# Aux_Lights_Power_Conversion.net
KiCad netlist of a schematic drawn in Altium Designer
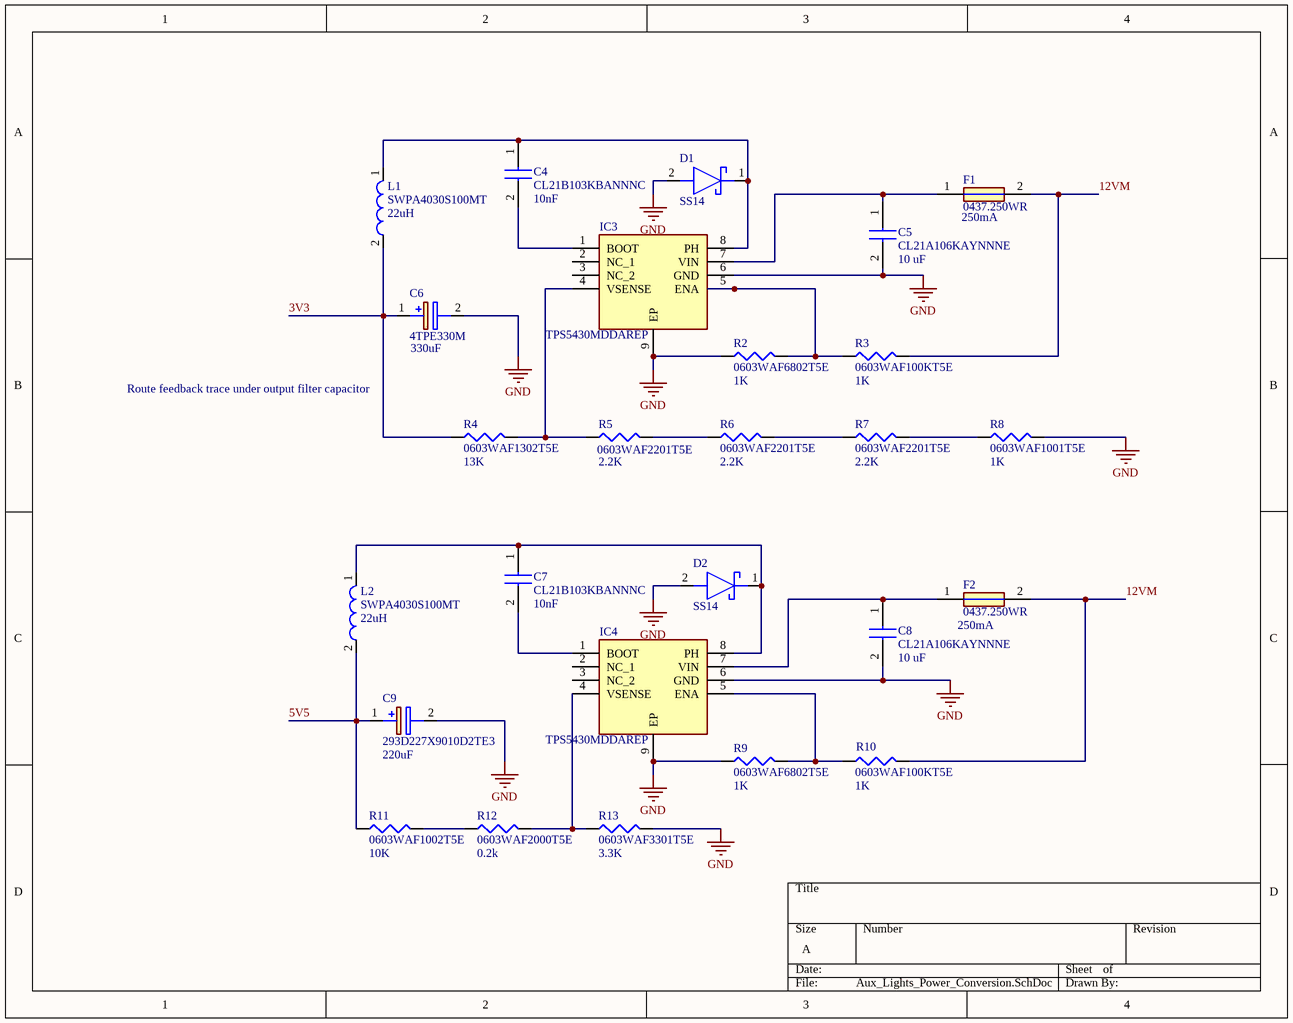
[diagram p0: Aux_Lights_Power_Conversion.SchDoc]

(export (version "E")
  (design (tool "Eeschema 10.0.6"))
  (components
    (comp (ref "C4")
      (value "CL21B103KBANNNC")
      (footprint "SteeringWheelParts:CAPC2012X65N")
      (description "Capacitor")
      (fields (field (name "ALTIUM_VALUE") "10nF"))
      (libsource (lib "SteeringWheelParts") (part "CL21B103KBANNNC"))
    )
    (comp (ref "C5")
      (value "CL21A106KAYNNNE")
      (footprint "SteeringWheelParts:CAPC2012X145N")
      (description "Capacitor")
      (fields (field (name "ALTIUM_VALUE") "10 uF"))
      (libsource (lib "*") (part "CL21A106KAYNNNE"))
    )
    (comp (ref "C6")
      (value "4TPE330M")
      (footprint "SG_Common:POSCAP_D12_D15_D15E_D2E_D2_D3L_D4")
      (description "Capacitor Polarised")
      (fields (field (name "ALTIUM_VALUE") "330uF"))
      (libsource (lib "*") (part "4TPE330M"))
    )
    (comp (ref "C7")
      (value "CL21B103KBANNNC")
      (footprint "SteeringWheelParts:CAPC2012X65N")
      (description "Capacitor")
      (fields (field (name "ALTIUM_VALUE") "10nF"))
      (libsource (lib "SteeringWheelParts") (part "CL21B103KBANNNC"))
    )
    (comp (ref "C8")
      (value "CL21A106KAYNNNE")
      (footprint "SteeringWheelParts:CAPC2012X145N")
      (description "Capacitor")
      (fields (field (name "ALTIUM_VALUE") "10 uF"))
      (libsource (lib "*") (part "CL21A106KAYNNNE"))
    )
    (comp (ref "C9")
      (value "293D227X9010D2TE3")
      (footprint "SteeringWheelParts:CAPPM7343X310N")
      (description "Capacitor Polarised")
      (fields (field (name "ALTIUM_VALUE") "220uF"))
      (libsource (lib "*") (part "293D227X9010D2TE3"))
    )
    (comp (ref "D1")
      (value "SS14")
      (footprint "SteeringWheelParts:DIONM5327X242N")
      (description "Schottky Diode")
      (libsource (lib "SteeringWheelParts") (part "SS14"))
    )
    (comp (ref "D2")
      (value "SS14")
      (footprint "SteeringWheelParts:DIONM5327X242N")
      (description "Schottky Diode")
      (libsource (lib "SteeringWheelParts") (part "SS14"))
    )
    (comp (ref "F1")
      (value "0437.250WR")
      (footprint "SteeringWheelParts:FUSC3216X86N")
      (description "Fuse")
      (fields (field (name "ALTIUM_VALUE") "250mA"))
      (libsource (lib "*") (part "0437.250WR"))
    )
    (comp (ref "F2")
      (value "0437.250WR")
      (footprint "SteeringWheelParts:FUSC3216X86N")
      (description "Fuse")
      (fields (field (name "ALTIUM_VALUE") "250mA"))
      (libsource (lib "*") (part "0437.250WR"))
    )
    (comp (ref "IC3")
      (value "TPS5430MDDAREP")
      (footprint "SteeringWheelParts:SOIC127P600X170-9N")
      (description "Integrated Circuit")
      (fields (field (name "MOUSER2 PART NUMBER") "595-TPS5430MDDAREP"))
      (libsource (lib "SteeringWheelParts") (part "TPS5430MDDAREP"))
    )
    (comp (ref "IC4")
      (value "TPS5430MDDAREP")
      (footprint "SteeringWheelParts:SOIC127P600X170-9N")
      (description "Integrated Circuit")
      (fields (field (name "MOUSER2 PART NUMBER") "595-TPS5430MDDAREP"))
      (libsource (lib "SteeringWheelParts") (part "TPS5430MDDAREP"))
    )
    (comp (ref "L1")
      (value "SWPA4030S100MT")
      (footprint "SWPA4030S100MT")
      (fields (field (name "ALTIUM_VALUE") "22uH"))
      (libsource (lib "SG_Common") (part "SWPA4030S100MT"))
    )
    (comp (ref "L2")
      (value "SWPA4030S100MT")
      (footprint "SWPA4030S100MT")
      (fields (field (name "ALTIUM_VALUE") "22uH"))
      (libsource (lib "SG_Common") (part "SWPA4030S100MT"))
    )
    (comp (ref "R2")
      (value "0603WAF6802T5E")
      (footprint "J1-0603")
      (description "Resistor")
      (fields (field (name "ALTIUM_VALUE") "1K") (field (name "PUBLISHER") "Altium Limited"))
      (libsource (lib "Miscellaneous Devices") (part "Res3"))
    )
    (comp (ref "R3")
      (value "0603WAF100KT5E")
      (footprint "J1-0603")
      (description "Resistor")
      (fields (field (name "ALTIUM_VALUE") "1K") (field (name "PUBLISHER") "Altium Limited"))
      (libsource (lib "Miscellaneous Devices") (part "Res3"))
    )
    (comp (ref "R4")
      (value "0603WAF1302T5E")
      (footprint "J1-0603")
      (description "Resistor")
      (fields (field (name "ALTIUM_VALUE") "13K") (field (name "PUBLISHER") "Altium Limited"))
      (libsource (lib "Miscellaneous Devices") (part "Res3"))
    )
    (comp (ref "R5")
      (value "0603WAF2201T5E")
      (footprint "J1-0603")
      (description "Resistor")
      (fields (field (name "ALTIUM_VALUE") "2.2K") (field (name "PUBLISHER") "Altium Limited"))
      (libsource (lib "Miscellaneous Devices") (part "Res3"))
    )
    (comp (ref "R6")
      (value "0603WAF2201T5E")
      (footprint "J1-0603")
      (description "Resistor")
      (fields (field (name "ALTIUM_VALUE") "2.2K") (field (name "PUBLISHER") "Altium Limited"))
      (libsource (lib "Miscellaneous Devices") (part "Res3"))
    )
    (comp (ref "R7")
      (value "0603WAF2201T5E")
      (footprint "J1-0603")
      (description "Resistor")
      (fields (field (name "ALTIUM_VALUE") "2.2K") (field (name "PUBLISHER") "Altium Limited"))
      (libsource (lib "Miscellaneous Devices") (part "Res3"))
    )
    (comp (ref "R8")
      (value "0603WAF1001T5E")
      (footprint "J1-0603")
      (description "Resistor")
      (fields (field (name "ALTIUM_VALUE") "1K") (field (name "PUBLISHER") "Altium Limited"))
      (libsource (lib "Miscellaneous Devices") (part "Res3"))
    )
    (comp (ref "R9")
      (value "0603WAF6802T5E")
      (footprint "J1-0603")
      (description "Resistor")
      (fields (field (name "ALTIUM_VALUE") "1K") (field (name "PUBLISHER") "Altium Limited"))
      (libsource (lib "Miscellaneous Devices") (part "Res3"))
    )
    (comp (ref "R10")
      (value "0603WAF100KT5E")
      (footprint "J1-0603")
      (description "Resistor")
      (fields (field (name "ALTIUM_VALUE") "1K") (field (name "PUBLISHER") "Altium Limited"))
      (libsource (lib "Miscellaneous Devices") (part "Res3"))
    )
    (comp (ref "R11")
      (value "0603WAF1002T5E")
      (footprint "J1-0603")
      (description "Resistor")
      (fields (field (name "ALTIUM_VALUE") "10K") (field (name "PUBLISHER") "Altium Limited"))
      (libsource (lib "Miscellaneous Devices") (part "Res3"))
    )
    (comp (ref "R12")
      (value "0603WAF2000T5E")
      (footprint "J1-0603")
      (description "Resistor")
      (fields (field (name "ALTIUM_VALUE") "0.2k") (field (name "PUBLISHER") "Altium Limited"))
      (libsource (lib "Miscellaneous Devices") (part "Res3"))
    )
    (comp (ref "R13")
      (value "0603WAF3301T5E")
      (footprint "J1-0603")
      (description "Resistor")
      (fields (field (name "ALTIUM_VALUE") "3.3K") (field (name "PUBLISHER") "Altium Limited"))
      (libsource (lib "Miscellaneous Devices") (part "Res3"))
    )
  )
  (nets
    (net (code "1") (name "/3V3") (class "Default")
      (node (ref "C6") (pin "1") (pinfunction "+_1") (pintype "passive"))
      (node (ref "L1") (pin "2") (pinfunction "2_2") (pintype "passive"))
      (node (ref "R4") (pin "1") (pinfunction "1_1") (pintype "passive"))
    )
    (net (code "2") (name "/5V5") (class "Default")
      (node (ref "C9") (pin "1") (pinfunction "+_1") (pintype "passive"))
      (node (ref "L2") (pin "2") (pinfunction "2_2") (pintype "passive"))
      (node (ref "R11") (pin "1") (pinfunction "1_1") (pintype "passive"))
    )
    (net (code "3") (name "/12VM") (class "Default")
      (node (ref "F1") (pin "2") (pinfunction "2_2") (pintype "passive"))
      (node (ref "F2") (pin "2") (pinfunction "2_2") (pintype "passive"))
      (node (ref "R10") (pin "2") (pinfunction "2_2") (pintype "passive"))
      (node (ref "R3") (pin "2") (pinfunction "2_2") (pintype "passive"))
    )
    (net (code "4") (name "GND") (class "Default")
      (node (ref "C5") (pin "2") (pinfunction "2_2") (pintype "passive"))
      (node (ref "C6") (pin "2") (pinfunction "-_2") (pintype "passive"))
      (node (ref "C8") (pin "2") (pinfunction "2_2") (pintype "passive"))
      (node (ref "C9") (pin "2") (pinfunction "-_2") (pintype "passive"))
      (node (ref "D1") (pin "2") (pinfunction "A_2") (pintype "passive"))
      (node (ref "D2") (pin "2") (pinfunction "A_2") (pintype "passive"))
      (node (ref "IC3") (pin "6") (pinfunction "GND_6") (pintype "passive"))
      (node (ref "IC3") (pin "9") (pinfunction "EP_9") (pintype "passive"))
      (node (ref "IC4") (pin "6") (pinfunction "GND_6") (pintype "passive"))
      (node (ref "IC4") (pin "9") (pinfunction "EP_9") (pintype "passive"))
      (node (ref "R13") (pin "2") (pinfunction "2_2") (pintype "passive"))
      (node (ref "R2") (pin "1") (pinfunction "1_1") (pintype "passive"))
      (node (ref "R8") (pin "2") (pinfunction "2_2") (pintype "passive"))
      (node (ref "R9") (pin "1") (pinfunction "1_1") (pintype "passive"))
    )
    (net (code "5") (name "Net-(D1-K)") (class "Default")
      (node (ref "C4") (pin "1") (pinfunction "1_1") (pintype "passive"))
      (node (ref "D1") (pin "1") (pinfunction "K_1") (pintype "passive"))
      (node (ref "IC3") (pin "8") (pinfunction "PH_8") (pintype "passive"))
      (node (ref "L1") (pin "1") (pinfunction "1_1") (pintype "passive"))
    )
    (net (code "6") (name "Net-(D2-K)") (class "Default")
      (node (ref "C7") (pin "1") (pinfunction "1_1") (pintype "passive"))
      (node (ref "D2") (pin "1") (pinfunction "K_1") (pintype "passive"))
      (node (ref "IC4") (pin "8") (pinfunction "PH_8") (pintype "passive"))
      (node (ref "L2") (pin "1") (pinfunction "1_1") (pintype "passive"))
    )
    (net (code "7") (name "Net-(IC3-BOOT)") (class "Default")
      (node (ref "C4") (pin "2") (pinfunction "2_2") (pintype "passive"))
      (node (ref "IC3") (pin "1") (pinfunction "BOOT_1") (pintype "passive"))
    )
    (net (code "8") (name "Net-(IC3-ENA)") (class "Default")
      (node (ref "IC3") (pin "5") (pinfunction "ENA_5") (pintype "passive"))
      (node (ref "R2") (pin "2") (pinfunction "2_2") (pintype "passive"))
      (node (ref "R3") (pin "1") (pinfunction "1_1") (pintype "passive"))
    )
    (net (code "9") (name "Net-(IC3-VIN)") (class "Default")
      (node (ref "C5") (pin "1") (pinfunction "1_1") (pintype "passive"))
      (node (ref "F1") (pin "1") (pinfunction "1_1") (pintype "passive"))
      (node (ref "IC3") (pin "7") (pinfunction "VIN_7") (pintype "passive"))
    )
    (net (code "10") (name "Net-(IC3-VSENSE)") (class "Default")
      (node (ref "IC3") (pin "4") (pinfunction "VSENSE_4") (pintype "passive"))
      (node (ref "R4") (pin "2") (pinfunction "2_2") (pintype "passive"))
      (node (ref "R5") (pin "1") (pinfunction "1_1") (pintype "passive"))
    )
    (net (code "11") (name "Net-(IC4-BOOT)") (class "Default")
      (node (ref "C7") (pin "2") (pinfunction "2_2") (pintype "passive"))
      (node (ref "IC4") (pin "1") (pinfunction "BOOT_1") (pintype "passive"))
    )
    (net (code "12") (name "Net-(IC4-ENA)") (class "Default")
      (node (ref "IC4") (pin "5") (pinfunction "ENA_5") (pintype "passive"))
      (node (ref "R10") (pin "1") (pinfunction "1_1") (pintype "passive"))
      (node (ref "R9") (pin "2") (pinfunction "2_2") (pintype "passive"))
    )
    (net (code "13") (name "Net-(IC4-VIN)") (class "Default")
      (node (ref "C8") (pin "1") (pinfunction "1_1") (pintype "passive"))
      (node (ref "F2") (pin "1") (pinfunction "1_1") (pintype "passive"))
      (node (ref "IC4") (pin "7") (pinfunction "VIN_7") (pintype "passive"))
    )
    (net (code "14") (name "Net-(IC4-VSENSE)") (class "Default")
      (node (ref "IC4") (pin "4") (pinfunction "VSENSE_4") (pintype "passive"))
      (node (ref "R12") (pin "2") (pinfunction "2_2") (pintype "passive"))
      (node (ref "R13") (pin "1") (pinfunction "1_1") (pintype "passive"))
    )
    (net (code "15") (name "Net-(R5-Pad2)") (class "Default")
      (node (ref "R5") (pin "2") (pinfunction "2_2") (pintype "passive"))
      (node (ref "R6") (pin "1") (pinfunction "1_1") (pintype "passive"))
    )
    (net (code "16") (name "Net-(R6-Pad2)") (class "Default")
      (node (ref "R6") (pin "2") (pinfunction "2_2") (pintype "passive"))
      (node (ref "R7") (pin "1") (pinfunction "1_1") (pintype "passive"))
    )
    (net (code "17") (name "Net-(R7-Pad2)") (class "Default")
      (node (ref "R7") (pin "2") (pinfunction "2_2") (pintype "passive"))
      (node (ref "R8") (pin "1") (pinfunction "1_1") (pintype "passive"))
    )
    (net (code "18") (name "Net-(R11-Pad2)") (class "Default")
      (node (ref "R11") (pin "2") (pinfunction "2_2") (pintype "passive"))
      (node (ref "R12") (pin "1") (pinfunction "1_1") (pintype "passive"))
    )
    (net (code "19") (name "unconnected-(IC3-NC_1-Pad2)") (class "Default")
      (node (ref "IC3") (pin "2") (pinfunction "NC_1_2") (pintype "passive"))
    )
    (net (code "20") (name "unconnected-(IC3-NC_2-Pad3)") (class "Default")
      (node (ref "IC3") (pin "3") (pinfunction "NC_2_3") (pintype "passive"))
    )
    (net (code "21") (name "unconnected-(IC4-NC_1-Pad2)") (class "Default")
      (node (ref "IC4") (pin "2") (pinfunction "NC_1_2") (pintype "passive"))
    )
    (net (code "22") (name "unconnected-(IC4-NC_2-Pad3)") (class "Default")
      (node (ref "IC4") (pin "3") (pinfunction "NC_2_3") (pintype "passive"))
    )
  )
)
